# Green_Pill_Sparkfun.net
KiCad netlist of a schematic drawn in EAGLE
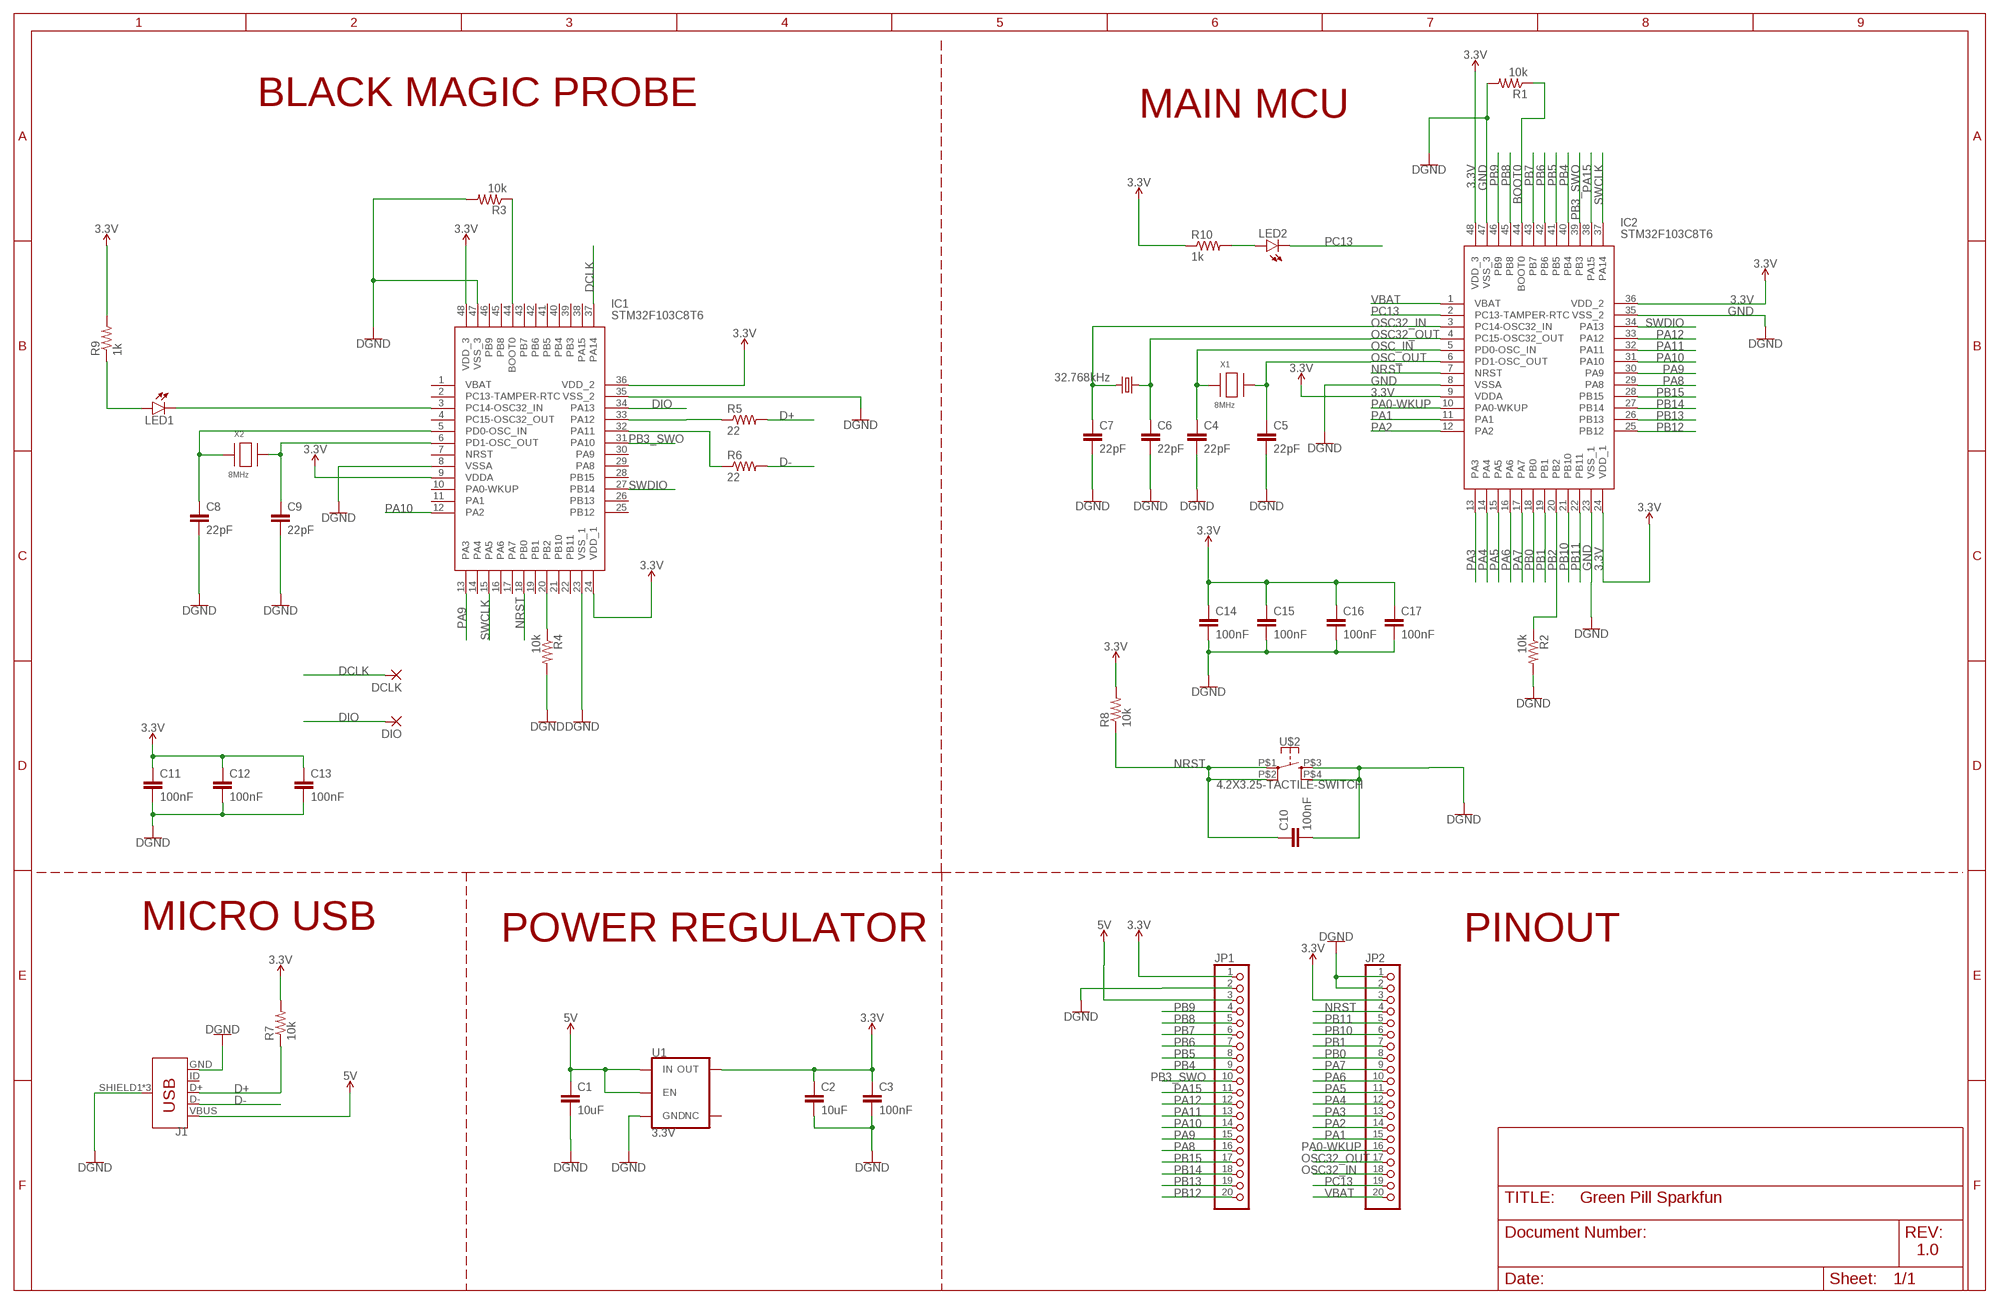
[diagram p0: schematic, sheet 1]

(export (version "E")
  (design (tool "Eeschema 10.0.6"))
  (components
    (comp (ref "C1")
      (value "10uF")
      (footprint "eagle-import:C0805")
      (libsource (lib "eagle-import") (part "C-EUC0805"))
    )
    (comp (ref "C2")
      (value "10uF")
      (footprint "eagle-import:C0805")
      (libsource (lib "eagle-import") (part "C-EUC0805"))
    )
    (comp (ref "C3")
      (value "100nF")
      (footprint "eagle-import:C0603")
      (libsource (lib "eagle-import") (part "C-EUC0603"))
    )
    (comp (ref "C4")
      (value "22pF")
      (footprint "eagle-import:C0603")
      (libsource (lib "eagle-import") (part "resistor_348_C-EUC0603"))
    )
    (comp (ref "C5")
      (value "22pF")
      (footprint "eagle-import:C0603")
      (libsource (lib "eagle-import") (part "resistor_348_C-EUC0603"))
    )
    (comp (ref "C6")
      (value "22pF")
      (footprint "eagle-import:C0603")
      (libsource (lib "eagle-import") (part "resistor_348_C-EUC0603"))
    )
    (comp (ref "C7")
      (value "22pF")
      (footprint "eagle-import:C0603")
      (libsource (lib "eagle-import") (part "resistor_348_C-EUC0603"))
    )
    (comp (ref "C8")
      (value "22pF")
      (footprint "eagle-import:C0603")
      (libsource (lib "eagle-import") (part "resistor_348_C-EUC0603"))
    )
    (comp (ref "C9")
      (value "22pF")
      (footprint "eagle-import:C0603")
      (libsource (lib "eagle-import") (part "resistor_348_C-EUC0603"))
    )
    (comp (ref "C10")
      (value "100nF")
      (footprint "eagle-import:C0603")
      (libsource (lib "eagle-import") (part "C-EUC0603"))
    )
    (comp (ref "C11")
      (value "100nF")
      (footprint "eagle-import:C0603")
      (libsource (lib "eagle-import") (part "C-EUC0603"))
    )
    (comp (ref "C12")
      (value "100nF")
      (footprint "eagle-import:C0603")
      (libsource (lib "eagle-import") (part "C-EUC0603"))
    )
    (comp (ref "C13")
      (value "100nF")
      (footprint "eagle-import:C0603")
      (libsource (lib "eagle-import") (part "C-EUC0603"))
    )
    (comp (ref "C14")
      (value "100nF")
      (footprint "eagle-import:C0603")
      (libsource (lib "eagle-import") (part "C-EUC0603"))
    )
    (comp (ref "C15")
      (value "100nF")
      (footprint "eagle-import:C0603")
      (libsource (lib "eagle-import") (part "C-EUC0603"))
    )
    (comp (ref "C16")
      (value "100nF")
      (footprint "eagle-import:C0603")
      (libsource (lib "eagle-import") (part "C-EUC0603"))
    )
    (comp (ref "C17")
      (value "100nF")
      (footprint "eagle-import:C0603")
      (libsource (lib "eagle-import") (part "C-EUC0603"))
    )
    (comp (ref "DCLK")
      (value "SMD2")
      (footprint "eagle-import:SMD1,27-2,54")
      (libsource (lib "eagle-import") (part "SMD2"))
    )
    (comp (ref "DIO")
      (value "SMD2")
      (footprint "eagle-import:SMD1,27-2,54")
      (libsource (lib "eagle-import") (part "SMD2"))
    )
    (comp (ref "IC1")
      (value "STM32F103C8T6")
      (footprint "eagle-import:QFP50P900X900X160-48N")
      (fields (field (name "MOUSER_PART_NUMBER") "511-STM32F103C8T6"))
      (libsource (lib "eagle-import") (part "STM32F103C8T6"))
    )
    (comp (ref "IC2")
      (value "STM32F103C8T6")
      (footprint "eagle-import:QFP50P900X900X160-48N")
      (fields (field (name "MOUSER_PART_NUMBER") "511-STM32F103C8T6"))
      (libsource (lib "eagle-import") (part "STM32F103C8T6"))
    )
    (comp (ref "J1")
      (value "USB_MICRO-B_FEMALE-SMT")
      (footprint "eagle-import:USB-B-MICRO-SMD")
      (libsource (lib "eagle-import") (part "USB_MICRO-B_FEMALE-SMT"))
    )
    (comp (ref "JP1")
      (value "PINHD-1X20")
      (footprint "eagle-import:1X20")
      (libsource (lib "eagle-import") (part "PINHD-1X20"))
    )
    (comp (ref "JP2")
      (value "PINHD-1X20")
      (footprint "eagle-import:1X20")
      (libsource (lib "eagle-import") (part "PINHD-1X20"))
    )
    (comp (ref "LED1")
      (value "LEDCHIP-LED0805")
      (footprint "eagle-import:CHIP-LED0805")
      (libsource (lib "eagle-import") (part "LEDCHIP-LED0805"))
    )
    (comp (ref "LED2")
      (value "LEDCHIP-LED0805")
      (footprint "eagle-import:CHIP-LED0805")
      (libsource (lib "eagle-import") (part "LEDCHIP-LED0805"))
    )
    (comp (ref "R1")
      (value "10k")
      (footprint "eagle-import:R0603")
      (libsource (lib "eagle-import") (part "R-US_R0603"))
    )
    (comp (ref "R2")
      (value "10k")
      (footprint "eagle-import:R0603")
      (libsource (lib "eagle-import") (part "R-US_R0603"))
    )
    (comp (ref "R3")
      (value "10k")
      (footprint "eagle-import:R0603")
      (libsource (lib "eagle-import") (part "R-US_R0603"))
    )
    (comp (ref "R4")
      (value "10k")
      (footprint "eagle-import:R0603")
      (libsource (lib "eagle-import") (part "R-US_R0603"))
    )
    (comp (ref "R5")
      (value "22")
      (footprint "eagle-import:R0603")
      (libsource (lib "eagle-import") (part "resistor_348_R-US_R0603"))
    )
    (comp (ref "R6")
      (value "22")
      (footprint "eagle-import:R0603")
      (libsource (lib "eagle-import") (part "resistor_348_R-US_R0603"))
    )
    (comp (ref "R7")
      (value "10k")
      (footprint "eagle-import:R0603")
      (libsource (lib "eagle-import") (part "resistor_348_R-US_R0603"))
    )
    (comp (ref "R8")
      (value "10k")
      (footprint "eagle-import:R0603")
      (libsource (lib "eagle-import") (part "R-US_R0603"))
    )
    (comp (ref "R9")
      (value "1k")
      (footprint "eagle-import:R0603")
      (libsource (lib "eagle-import") (part "R-US_R0603"))
    )
    (comp (ref "R10")
      (value "1k")
      (footprint "eagle-import:R0603")
      (libsource (lib "eagle-import") (part "R-US_R0603"))
    )
    (comp (ref "U$1")
      (value "32.768kHz")
      (footprint "eagle-import:3.2X1.5")
      (libsource (lib "eagle-import") (part "KX-327"))
    )
    (comp (ref "U$2")
      (value "4.2X3.25-TACTILE-SWITCH")
      (footprint "eagle-import:4.2X3.25")
      (libsource (lib "eagle-import") (part "4.2X3.25-TACTILE-SWITCH"))
    )
    (comp (ref "U1")
      (value "3.3V")
      (footprint "eagle-import:SOT23-5")
      (libsource (lib "eagle-import") (part "V_REG_AP2112K-3.3V"))
    )
    (comp (ref "X1")
      (value "8MHz")
      (footprint "eagle-import:NX5032")
      (libsource (lib "eagle-import") (part "XTALNX5032"))
    )
    (comp (ref "X2")
      (value "8MHz")
      (footprint "eagle-import:NX5032")
      (libsource (lib "eagle-import") (part "XTALNX5032"))
    )
  )
  (nets
    (net (code "1") (name "/BOOT0") (class "Default")
      (node (ref "IC2") (pin "44") (pinfunction "BOOT0_44") (pintype "bidirectional"))
      (node (ref "R1") (pin "1") (pinfunction "1_1") (pintype "passive"))
    )
    (net (code "2") (name "/D+") (class "Default")
      (node (ref "J1") (pin "D+") (pinfunction "D+_D+") (pintype "bidirectional"))
      (node (ref "R5") (pin "2") (pinfunction "2_2") (pintype "passive"))
      (node (ref "R7") (pin "1") (pinfunction "1_1") (pintype "passive"))
    )
    (net (code "3") (name "/D-") (class "Default")
      (node (ref "J1") (pin "D-") (pinfunction "D-_D-") (pintype "bidirectional"))
      (node (ref "R6") (pin "2") (pinfunction "2_2") (pintype "passive"))
    )
    (net (code "4") (name "/DCLK") (class "Default")
      (node (ref "DCLK") (pin "1") (pinfunction "P_1") (pintype "passive"))
      (node (ref "IC1") (pin "37") (pinfunction "PA14_37") (pintype "bidirectional"))
    )
    (net (code "5") (name "/DIO") (class "Default")
      (node (ref "DIO") (pin "1") (pinfunction "P_1") (pintype "passive"))
      (node (ref "IC1") (pin "34") (pinfunction "PA13_34") (pintype "bidirectional"))
    )
    (net (code "6") (name "/NRST") (class "Default")
      (node (ref "C10") (pin "1") (pinfunction "1_1") (pintype "passive"))
      (node (ref "IC1") (pin "18") (pinfunction "PB0_18") (pintype "bidirectional"))
      (node (ref "IC2") (pin "7") (pinfunction "NRST_7") (pintype "input"))
      (node (ref "JP2") (pin "4") (pinfunction "4_4") (pintype "passive"))
      (node (ref "R8") (pin "1") (pinfunction "1_1") (pintype "passive"))
      (node (ref "U$2") (pin "P$1") (pinfunction "1_P$1") (pintype "passive"))
      (node (ref "U$2") (pin "P$2") (pinfunction "2_P$2") (pintype "passive"))
    )
    (net (code "7") (name "/OSC32_IN") (class "Default")
      (node (ref "C7") (pin "1") (pinfunction "1_1") (pintype "passive"))
      (node (ref "IC2") (pin "3") (pinfunction "PC14-OSC32_IN_3") (pintype "input"))
      (node (ref "JP2") (pin "18") (pinfunction "18_18") (pintype "passive"))
      (node (ref "U$1") (pin "2") (pinfunction "2_2") (pintype "passive"))
    )
    (net (code "8") (name "/OSC32_OUT") (class "Default")
      (node (ref "C6") (pin "1") (pinfunction "1_1") (pintype "passive"))
      (node (ref "IC2") (pin "4") (pinfunction "PC15-OSC32_OUT_4") (pintype "output"))
      (node (ref "JP2") (pin "17") (pinfunction "17_17") (pintype "passive"))
      (node (ref "U$1") (pin "1") (pinfunction "1_1") (pintype "passive"))
    )
    (net (code "9") (name "/OSC_IN") (class "Default")
      (node (ref "C4") (pin "1") (pinfunction "1_1") (pintype "passive"))
      (node (ref "IC2") (pin "5") (pinfunction "PD0-OSC_IN_5") (pintype "input"))
      (node (ref "X1") (pin "P$1") (pinfunction "P$1_P$1") (pintype "bidirectional"))
    )
    (net (code "10") (name "/OSC_OUT") (class "Default")
      (node (ref "C5") (pin "1") (pinfunction "1_1") (pintype "passive"))
      (node (ref "IC2") (pin "6") (pinfunction "PD1-OSC_OUT_6") (pintype "output"))
      (node (ref "X1") (pin "P$2") (pinfunction "P$2_P$2") (pintype "bidirectional"))
    )
    (net (code "11") (name "/PA0-WKUP") (class "Default")
      (node (ref "IC2") (pin "10") (pinfunction "PA0-WKUP_10") (pintype "bidirectional"))
      (node (ref "JP2") (pin "16") (pinfunction "16_16") (pintype "passive"))
    )
    (net (code "12") (name "/PA1") (class "Default")
      (node (ref "IC2") (pin "11") (pinfunction "PA1_11") (pintype "bidirectional"))
      (node (ref "JP2") (pin "15") (pinfunction "15_15") (pintype "passive"))
    )
    (net (code "13") (name "/PA2") (class "Default")
      (node (ref "IC2") (pin "12") (pinfunction "PA2_12") (pintype "bidirectional"))
      (node (ref "JP2") (pin "14") (pinfunction "14_14") (pintype "passive"))
    )
    (net (code "14") (name "/PA3") (class "Default")
      (node (ref "IC2") (pin "13") (pinfunction "PA3_13") (pintype "bidirectional"))
      (node (ref "JP2") (pin "13") (pinfunction "13_13") (pintype "passive"))
    )
    (net (code "15") (name "/PA4") (class "Default")
      (node (ref "IC2") (pin "14") (pinfunction "PA4_14") (pintype "bidirectional"))
      (node (ref "JP2") (pin "12") (pinfunction "12_12") (pintype "passive"))
    )
    (net (code "16") (name "/PA5") (class "Default")
      (node (ref "IC2") (pin "15") (pinfunction "PA5_15") (pintype "bidirectional"))
      (node (ref "JP2") (pin "11") (pinfunction "11_11") (pintype "passive"))
    )
    (net (code "17") (name "/PA6") (class "Default")
      (node (ref "IC2") (pin "16") (pinfunction "PA6_16") (pintype "bidirectional"))
      (node (ref "JP2") (pin "10") (pinfunction "10_10") (pintype "passive"))
    )
    (net (code "18") (name "/PA7") (class "Default")
      (node (ref "IC2") (pin "17") (pinfunction "PA7_17") (pintype "bidirectional"))
      (node (ref "JP2") (pin "9") (pinfunction "9_9") (pintype "passive"))
    )
    (net (code "19") (name "/PA8") (class "Default")
      (node (ref "IC2") (pin "29") (pinfunction "PA8_29") (pintype "bidirectional"))
      (node (ref "JP1") (pin "16") (pinfunction "16_16") (pintype "passive"))
    )
    (net (code "20") (name "/PA9") (class "Default")
      (node (ref "IC1") (pin "13") (pinfunction "PA3_13") (pintype "bidirectional"))
      (node (ref "IC2") (pin "30") (pinfunction "PA9_30") (pintype "bidirectional"))
      (node (ref "JP1") (pin "15") (pinfunction "15_15") (pintype "passive"))
    )
    (net (code "21") (name "/PA10") (class "Default")
      (node (ref "IC1") (pin "12") (pinfunction "PA2_12") (pintype "bidirectional"))
      (node (ref "IC2") (pin "31") (pinfunction "PA10_31") (pintype "bidirectional"))
      (node (ref "JP1") (pin "14") (pinfunction "14_14") (pintype "passive"))
    )
    (net (code "22") (name "/PA11") (class "Default")
      (node (ref "IC2") (pin "32") (pinfunction "PA11_32") (pintype "bidirectional"))
      (node (ref "JP1") (pin "13") (pinfunction "13_13") (pintype "passive"))
    )
    (net (code "23") (name "/PA12") (class "Default")
      (node (ref "IC2") (pin "33") (pinfunction "PA12_33") (pintype "bidirectional"))
      (node (ref "JP1") (pin "12") (pinfunction "12_12") (pintype "passive"))
    )
    (net (code "24") (name "/PA15") (class "Default")
      (node (ref "IC2") (pin "38") (pinfunction "PA15_38") (pintype "bidirectional"))
      (node (ref "JP1") (pin "11") (pinfunction "11_11") (pintype "passive"))
    )
    (net (code "25") (name "/PB0") (class "Default")
      (node (ref "IC2") (pin "18") (pinfunction "PB0_18") (pintype "bidirectional"))
      (node (ref "JP2") (pin "8") (pinfunction "8_8") (pintype "passive"))
    )
    (net (code "26") (name "/PB1") (class "Default")
      (node (ref "IC2") (pin "19") (pinfunction "PB1_19") (pintype "bidirectional"))
      (node (ref "JP2") (pin "7") (pinfunction "7_7") (pintype "passive"))
    )
    (net (code "27") (name "/PB2") (class "Default")
      (node (ref "IC2") (pin "20") (pinfunction "PB2_20") (pintype "bidirectional"))
      (node (ref "R2") (pin "1") (pinfunction "1_1") (pintype "passive"))
    )
    (net (code "28") (name "/PB3_SWO") (class "Default")
      (node (ref "IC1") (pin "31") (pinfunction "PA10_31") (pintype "bidirectional"))
      (node (ref "IC2") (pin "39") (pinfunction "PB3_39") (pintype "bidirectional"))
      (node (ref "JP1") (pin "10") (pinfunction "10_10") (pintype "passive"))
    )
    (net (code "29") (name "/PB4") (class "Default")
      (node (ref "IC2") (pin "40") (pinfunction "PB4_40") (pintype "bidirectional"))
      (node (ref "JP1") (pin "9") (pinfunction "9_9") (pintype "passive"))
    )
    (net (code "30") (name "/PB5") (class "Default")
      (node (ref "IC2") (pin "41") (pinfunction "PB5_41") (pintype "bidirectional"))
      (node (ref "JP1") (pin "8") (pinfunction "8_8") (pintype "passive"))
    )
    (net (code "31") (name "/PB6") (class "Default")
      (node (ref "IC2") (pin "42") (pinfunction "PB6_42") (pintype "bidirectional"))
      (node (ref "JP1") (pin "7") (pinfunction "7_7") (pintype "passive"))
    )
    (net (code "32") (name "/PB7") (class "Default")
      (node (ref "IC2") (pin "43") (pinfunction "PB7_43") (pintype "bidirectional"))
      (node (ref "JP1") (pin "6") (pinfunction "6_6") (pintype "passive"))
    )
    (net (code "33") (name "/PB8") (class "Default")
      (node (ref "IC2") (pin "45") (pinfunction "PB8_45") (pintype "bidirectional"))
      (node (ref "JP1") (pin "5") (pinfunction "5_5") (pintype "passive"))
    )
    (net (code "34") (name "/PB9") (class "Default")
      (node (ref "IC2") (pin "46") (pinfunction "PB9_46") (pintype "bidirectional"))
      (node (ref "JP1") (pin "4") (pinfunction "4_4") (pintype "passive"))
    )
    (net (code "35") (name "/PB10") (class "Default")
      (node (ref "IC2") (pin "21") (pinfunction "PB10_21") (pintype "bidirectional"))
      (node (ref "JP2") (pin "6") (pinfunction "6_6") (pintype "passive"))
    )
    (net (code "36") (name "/PB11") (class "Default")
      (node (ref "IC2") (pin "22") (pinfunction "PB11_22") (pintype "bidirectional"))
      (node (ref "JP2") (pin "5") (pinfunction "5_5") (pintype "passive"))
    )
    (net (code "37") (name "/PB12") (class "Default")
      (node (ref "IC2") (pin "25") (pinfunction "PB12_25") (pintype "bidirectional"))
      (node (ref "JP1") (pin "20") (pinfunction "20_20") (pintype "passive"))
    )
    (net (code "38") (name "/PB13") (class "Default")
      (node (ref "IC2") (pin "26") (pinfunction "PB13_26") (pintype "bidirectional"))
      (node (ref "JP1") (pin "19") (pinfunction "19_19") (pintype "passive"))
    )
    (net (code "39") (name "/PB14") (class "Default")
      (node (ref "IC2") (pin "27") (pinfunction "PB14_27") (pintype "bidirectional"))
      (node (ref "JP1") (pin "18") (pinfunction "18_18") (pintype "passive"))
    )
    (net (code "40") (name "/PB15") (class "Default")
      (node (ref "IC2") (pin "28") (pinfunction "PB15_28") (pintype "bidirectional"))
      (node (ref "JP1") (pin "17") (pinfunction "17_17") (pintype "passive"))
    )
    (net (code "41") (name "/PC13") (class "Default")
      (node (ref "IC2") (pin "2") (pinfunction "PC13-TAMPER-RTC_2") (pintype "bidirectional"))
      (node (ref "JP2") (pin "19") (pinfunction "19_19") (pintype "passive"))
      (node (ref "LED2") (pin "C") (pinfunction "C_C") (pintype "passive"))
    )
    (net (code "42") (name "/SWCLK") (class "Default")
      (node (ref "IC1") (pin "15") (pinfunction "PA5_15") (pintype "bidirectional"))
      (node (ref "IC2") (pin "37") (pinfunction "PA14_37") (pintype "bidirectional"))
    )
    (net (code "43") (name "/SWDIO") (class "Default")
      (node (ref "IC1") (pin "27") (pinfunction "PB14_27") (pintype "bidirectional"))
      (node (ref "IC2") (pin "34") (pinfunction "PA13_34") (pintype "bidirectional"))
    )
    (net (code "44") (name "/VBAT") (class "Default")
      (node (ref "IC2") (pin "1") (pinfunction "VBAT_1") (pintype "bidirectional"))
      (node (ref "JP2") (pin "20") (pinfunction "20_20") (pintype "passive"))
    )
    (net (code "45") (name "3.3V") (class "Default")
      (node (ref "C11") (pin "1") (pinfunction "1_1") (pintype "passive"))
      (node (ref "C12") (pin "1") (pinfunction "1_1") (pintype "passive"))
      (node (ref "C13") (pin "1") (pinfunction "1_1") (pintype "passive"))
      (node (ref "C14") (pin "1") (pinfunction "1_1") (pintype "passive"))
      (node (ref "C15") (pin "1") (pinfunction "1_1") (pintype "passive"))
      (node (ref "C16") (pin "1") (pinfunction "1_1") (pintype "passive"))
      (node (ref "C17") (pin "1") (pinfunction "1_1") (pintype "passive"))
      (node (ref "C2") (pin "1") (pinfunction "1_1") (pintype "passive"))
      (node (ref "C3") (pin "1") (pinfunction "1_1") (pintype "passive"))
      (node (ref "IC1") (pin "24") (pinfunction "VDD_1_24") (pintype "power_in"))
      (node (ref "IC1") (pin "36") (pinfunction "VDD_2_36") (pintype "power_in"))
      (node (ref "IC1") (pin "48") (pinfunction "VDD_3_48") (pintype "power_in"))
      (node (ref "IC1") (pin "9") (pinfunction "VDDA_9") (pintype "power_in"))
      (node (ref "IC2") (pin "24") (pinfunction "VDD_1_24") (pintype "power_in"))
      (node (ref "IC2") (pin "36") (pinfunction "VDD_2_36") (pintype "power_in"))
      (node (ref "IC2") (pin "48") (pinfunction "VDD_3_48") (pintype "power_in"))
      (node (ref "IC2") (pin "9") (pinfunction "VDDA_9") (pintype "power_in"))
      (node (ref "JP1") (pin "1") (pinfunction "1_1") (pintype "passive"))
      (node (ref "JP2") (pin "3") (pinfunction "3_3") (pintype "passive"))
      (node (ref "R10") (pin "1") (pinfunction "1_1") (pintype "passive"))
      (node (ref "R7") (pin "2") (pinfunction "2_2") (pintype "passive"))
      (node (ref "R8") (pin "2") (pinfunction "2_2") (pintype "passive"))
      (node (ref "R9") (pin "2") (pinfunction "2_2") (pintype "passive"))
      (node (ref "U1") (pin "5") (pinfunction "OUT_5") (pintype "passive"))
    )
    (net (code "46") (name "5V") (class "Default")
      (node (ref "C1") (pin "1") (pinfunction "1_1") (pintype "passive"))
      (node (ref "J1") (pin "VBUS") (pinfunction "VBUS_VBUS") (pintype "power_in"))
      (node (ref "JP1") (pin "3") (pinfunction "3_3") (pintype "passive"))
      (node (ref "U1") (pin "1") (pinfunction "IN_1") (pintype "input"))
      (node (ref "U1") (pin "3") (pinfunction "EN_3") (pintype "input"))
    )
    (net (code "47") (name "DGND") (class "Default")
      (node (ref "C1") (pin "2") (pinfunction "2_2") (pintype "passive"))
      (node (ref "C10") (pin "2") (pinfunction "2_2") (pintype "passive"))
      (node (ref "C11") (pin "2") (pinfunction "2_2") (pintype "passive"))
      (node (ref "C12") (pin "2") (pinfunction "2_2") (pintype "passive"))
      (node (ref "C13") (pin "2") (pinfunction "2_2") (pintype "passive"))
      (node (ref "C14") (pin "2") (pinfunction "2_2") (pintype "passive"))
      (node (ref "C15") (pin "2") (pinfunction "2_2") (pintype "passive"))
      (node (ref "C16") (pin "2") (pinfunction "2_2") (pintype "passive"))
      (node (ref "C17") (pin "2") (pinfunction "2_2") (pintype "passive"))
      (node (ref "C2") (pin "2") (pinfunction "2_2") (pintype "passive"))
      (node (ref "C3") (pin "2") (pinfunction "2_2") (pintype "passive"))
      (node (ref "C4") (pin "2") (pinfunction "2_2") (pintype "passive"))
      (node (ref "C5") (pin "2") (pinfunction "2_2") (pintype "passive"))
      (node (ref "C6") (pin "2") (pinfunction "2_2") (pintype "passive"))
      (node (ref "C7") (pin "2") (pinfunction "2_2") (pintype "passive"))
      (node (ref "C8") (pin "2") (pinfunction "2_2") (pintype "passive"))
      (node (ref "C9") (pin "2") (pinfunction "2_2") (pintype "passive"))
      (node (ref "IC1") (pin "23") (pinfunction "VSS_1_23") (pintype "power_in"))
      (node (ref "IC1") (pin "35") (pinfunction "VSS_2_35") (pintype "power_in"))
      (node (ref "IC1") (pin "47") (pinfunction "VSS_3_47") (pintype "power_in"))
      (node (ref "IC1") (pin "8") (pinfunction "VSSA_8") (pintype "power_in"))
      (node (ref "IC2") (pin "23") (pinfunction "VSS_1_23") (pintype "power_in"))
      (node (ref "IC2") (pin "35") (pinfunction "VSS_2_35") (pintype "power_in"))
      (node (ref "IC2") (pin "47") (pinfunction "VSS_3_47") (pintype "power_in"))
      (node (ref "IC2") (pin "8") (pinfunction "VSSA_8") (pintype "power_in"))
      (node (ref "J1") (pin "GND") (pinfunction "GND_GND") (pintype "power_in"))
      (node (ref "J1") (pin "SHIELD1") (pinfunction "SHIELD_SHIELD1") (pintype "bidirectional"))
      (node (ref "J1") (pin "SHIELD2") (pinfunction "SHIELD_SHIELD2") (pintype "bidirectional"))
      (node (ref "J1") (pin "SHIELD3") (pinfunction "SHIELD_SHIELD3") (pintype "bidirectional"))
      (node (ref "JP1") (pin "2") (pinfunction "2_2") (pintype "passive"))
      (node (ref "JP2") (pin "1") (pinfunction "1_1") (pintype "passive"))
      (node (ref "JP2") (pin "2") (pinfunction "2_2") (pintype "passive"))
      (node (ref "R1") (pin "2") (pinfunction "2_2") (pintype "passive"))
      (node (ref "R2") (pin "2") (pinfunction "2_2") (pintype "passive"))
      (node (ref "R3") (pin "2") (pinfunction "2_2") (pintype "passive"))
      (node (ref "R4") (pin "2") (pinfunction "2_2") (pintype "passive"))
      (node (ref "U$2") (pin "P$3") (pinfunction "3_P$3") (pintype "passive"))
      (node (ref "U$2") (pin "P$4") (pinfunction "4_P$4") (pintype "passive"))
      (node (ref "U1") (pin "2") (pinfunction "GND_2") (pintype "input"))
    )
    (net (code "48") (name "Net-(IC1-BOOT0)") (class "Default")
      (node (ref "IC1") (pin "44") (pinfunction "BOOT0_44") (pintype "bidirectional"))
      (node (ref "R3") (pin "1") (pinfunction "1_1") (pintype "passive"))
    )
    (net (code "49") (name "Net-(IC1-PA11)") (class "Default")
      (node (ref "IC1") (pin "32") (pinfunction "PA11_32") (pintype "bidirectional"))
      (node (ref "R6") (pin "1") (pinfunction "1_1") (pintype "passive"))
    )
    (net (code "50") (name "Net-(IC1-PA12)") (class "Default")
      (node (ref "IC1") (pin "33") (pinfunction "PA12_33") (pintype "bidirectional"))
      (node (ref "R5") (pin "1") (pinfunction "1_1") (pintype "passive"))
    )
    (net (code "51") (name "Net-(IC1-PB2)") (class "Default")
      (node (ref "IC1") (pin "20") (pinfunction "PB2_20") (pintype "bidirectional"))
      (node (ref "R4") (pin "1") (pinfunction "1_1") (pintype "passive"))
    )
    (net (code "52") (name "Net-(IC1-PC14-OSC32_IN)") (class "Default")
      (node (ref "IC1") (pin "3") (pinfunction "PC14-OSC32_IN_3") (pintype "input"))
      (node (ref "LED1") (pin "C") (pinfunction "C_C") (pintype "passive"))
    )
    (net (code "53") (name "Net-(IC1-PD0-OSC_IN)") (class "Default")
      (node (ref "C8") (pin "1") (pinfunction "1_1") (pintype "passive"))
      (node (ref "IC1") (pin "5") (pinfunction "PD0-OSC_IN_5") (pintype "input"))
      (node (ref "X2") (pin "P$1") (pinfunction "P$1_P$1") (pintype "bidirectional"))
    )
    (net (code "54") (name "Net-(IC1-PD1-OSC_OUT)") (class "Default")
      (node (ref "C9") (pin "1") (pinfunction "1_1") (pintype "passive"))
      (node (ref "IC1") (pin "6") (pinfunction "PD1-OSC_OUT_6") (pintype "output"))
      (node (ref "X2") (pin "P$2") (pinfunction "P$2_P$2") (pintype "bidirectional"))
    )
    (net (code "55") (name "Net-(LED1-PadA)") (class "Default")
      (node (ref "LED1") (pin "A") (pinfunction "A_A") (pintype "passive"))
      (node (ref "R9") (pin "1") (pinfunction "1_1") (pintype "passive"))
    )
    (net (code "56") (name "Net-(LED2-PadA)") (class "Default")
      (node (ref "LED2") (pin "A") (pinfunction "A_A") (pintype "passive"))
      (node (ref "R10") (pin "2") (pinfunction "2_2") (pintype "passive"))
    )
    (net (code "57") (name "unconnected-(IC1-NRST-Pad7)") (class "Default")
      (node (ref "IC1") (pin "7") (pinfunction "NRST_7") (pintype "input"))
    )
    (net (code "58") (name "unconnected-(IC1-PA0-WKUP-Pad10)") (class "Default")
      (node (ref "IC1") (pin "10") (pinfunction "PA0-WKUP_10") (pintype "bidirectional"))
    )
    (net (code "59") (name "unconnected-(IC1-PA1-Pad11)") (class "Default")
      (node (ref "IC1") (pin "11") (pinfunction "PA1_11") (pintype "bidirectional"))
    )
    (net (code "60") (name "unconnected-(IC1-PA4-Pad14)") (class "Default")
      (node (ref "IC1") (pin "14") (pinfunction "PA4_14") (pintype "bidirectional"))
    )
    (net (code "61") (name "unconnected-(IC1-PA6-Pad16)") (class "Default")
      (node (ref "IC1") (pin "16") (pinfunction "PA6_16") (pintype "bidirectional"))
    )
    (net (code "62") (name "unconnected-(IC1-PA7-Pad17)") (class "Default")
      (node (ref "IC1") (pin "17") (pinfunction "PA7_17") (pintype "bidirectional"))
    )
    (net (code "63") (name "unconnected-(IC1-PA8-Pad29)") (class "Default")
      (node (ref "IC1") (pin "29") (pinfunction "PA8_29") (pintype "bidirectional"))
    )
    (net (code "64") (name "unconnected-(IC1-PA9-Pad30)") (class "Default")
      (node (ref "IC1") (pin "30") (pinfunction "PA9_30") (pintype "bidirectional"))
    )
    (net (code "65") (name "unconnected-(IC1-PA15-Pad38)") (class "Default")
      (node (ref "IC1") (pin "38") (pinfunction "PA15_38") (pintype "bidirectional"))
    )
    (net (code "66") (name "unconnected-(IC1-PB1-Pad19)") (class "Default")
      (node (ref "IC1") (pin "19") (pinfunction "PB1_19") (pintype "bidirectional"))
    )
    (net (code "67") (name "unconnected-(IC1-PB3-Pad39)") (class "Default")
      (node (ref "IC1") (pin "39") (pinfunction "PB3_39") (pintype "bidirectional"))
    )
    (net (code "68") (name "unconnected-(IC1-PB4-Pad40)") (class "Default")
      (node (ref "IC1") (pin "40") (pinfunction "PB4_40") (pintype "bidirectional"))
    )
    (net (code "69") (name "unconnected-(IC1-PB5-Pad41)") (class "Default")
      (node (ref "IC1") (pin "41") (pinfunction "PB5_41") (pintype "bidirectional"))
    )
    (net (code "70") (name "unconnected-(IC1-PB6-Pad42)") (class "Default")
      (node (ref "IC1") (pin "42") (pinfunction "PB6_42") (pintype "bidirectional"))
    )
    (net (code "71") (name "unconnected-(IC1-PB7-Pad43)") (class "Default")
      (node (ref "IC1") (pin "43") (pinfunction "PB7_43") (pintype "bidirectional"))
    )
    (net (code "72") (name "unconnected-(IC1-PB8-Pad45)") (class "Default")
      (node (ref "IC1") (pin "45") (pinfunction "PB8_45") (pintype "bidirectional"))
    )
    (net (code "73") (name "unconnected-(IC1-PB9-Pad46)") (class "Default")
      (node (ref "IC1") (pin "46") (pinfunction "PB9_46") (pintype "bidirectional"))
    )
    (net (code "74") (name "unconnected-(IC1-PB10-Pad21)") (class "Default")
      (node (ref "IC1") (pin "21") (pinfunction "PB10_21") (pintype "bidirectional"))
    )
    (net (code "75") (name "unconnected-(IC1-PB11-Pad22)") (class "Default")
      (node (ref "IC1") (pin "22") (pinfunction "PB11_22") (pintype "bidirectional"))
    )
    (net (code "76") (name "unconnected-(IC1-PB12-Pad25)") (class "Default")
      (node (ref "IC1") (pin "25") (pinfunction "PB12_25") (pintype "bidirectional"))
    )
    (net (code "77") (name "unconnected-(IC1-PB13-Pad26)") (class "Default")
      (node (ref "IC1") (pin "26") (pinfunction "PB13_26") (pintype "bidirectional"))
    )
    (net (code "78") (name "unconnected-(IC1-PB15-Pad28)") (class "Default")
      (node (ref "IC1") (pin "28") (pinfunction "PB15_28") (pintype "bidirectional"))
    )
    (net (code "79") (name "unconnected-(IC1-PC13-TAMPER-RTC-Pad2)") (class "Default")
      (node (ref "IC1") (pin "2") (pinfunction "PC13-TAMPER-RTC_2") (pintype "bidirectional"))
    )
    (net (code "80") (name "unconnected-(IC1-PC15-OSC32_OUT-Pad4)") (class "Default")
      (node (ref "IC1") (pin "4") (pinfunction "PC15-OSC32_OUT_4") (pintype "output"))
    )
    (net (code "81") (name "unconnected-(IC1-VBAT-Pad1)") (class "Default")
      (node (ref "IC1") (pin "1") (pinfunction "VBAT_1") (pintype "bidirectional"))
    )
    (net (code "82") (name "unconnected-(J1-PadID)") (class "Default")
      (node (ref "J1") (pin "ID") (pinfunction "ID_ID") (pintype "bidirectional"))
    )
    (net (code "83") (name "unconnected-(U1-NC-Pad4)") (class "Default")
      (node (ref "U1") (pin "4") (pinfunction "NC_4") (pintype "no_connect"))
    )
  )
)
